# OpenPCR-combined-blockfront.net
KiCad netlist of a schematic drawn in EAGLE
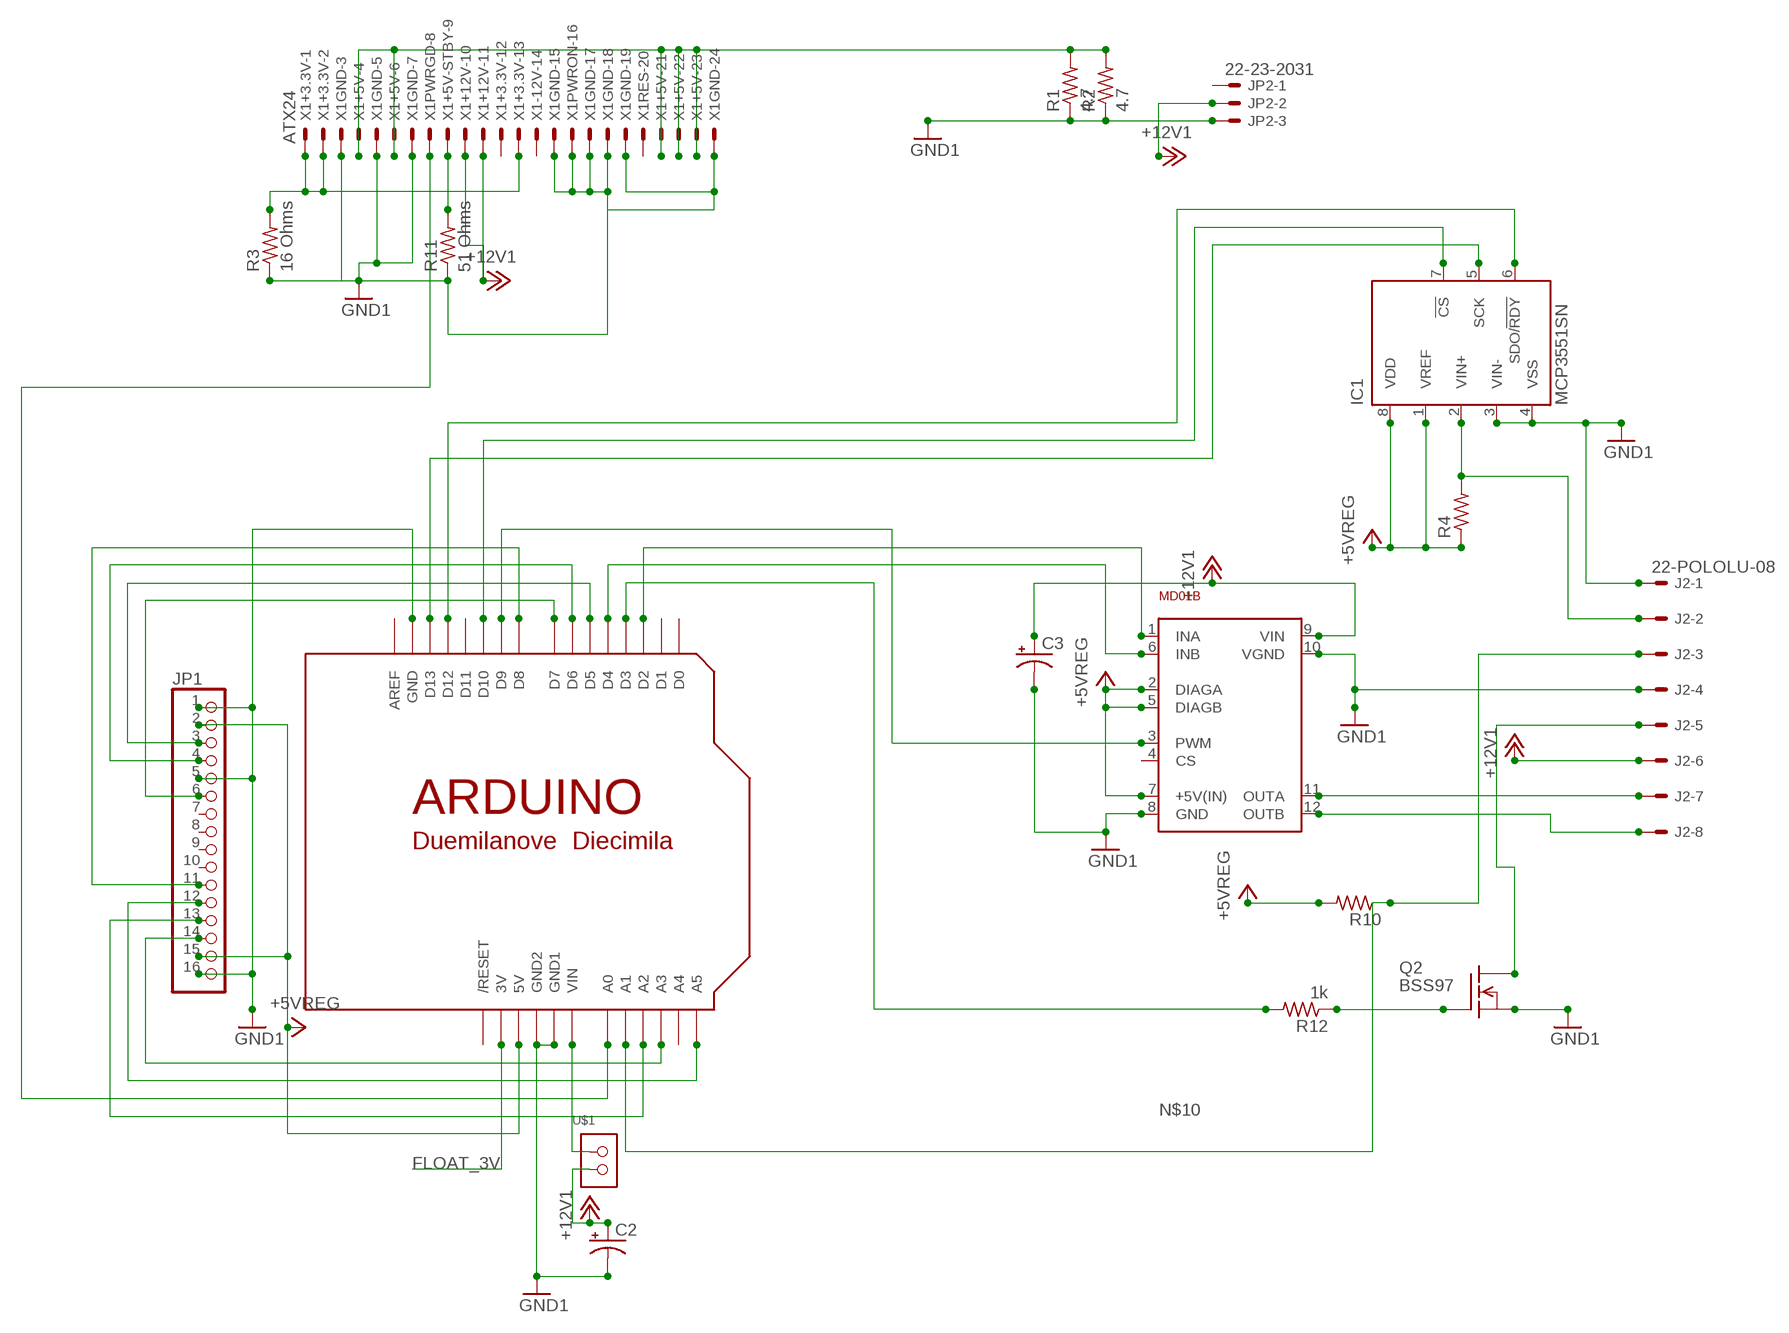
[diagram p0: schematic, sheet 1]

(export (version "E")
  (design (tool "Eeschema 10.0.6"))
  (components
    (comp (ref "C2")
      (value "CPOL-USE5-8.5")
      (footprint "eagle-import:E5-8,5")
      (libsource (lib "eagle-import") (part "CPOL-USE5-8.5"))
    )
    (comp (ref "C3")
      (value "CPOL-USE5-13")
      (footprint "eagle-import:E5-13")
      (libsource (lib "eagle-import") (part "CPOL-USE5-13"))
    )
    (comp (ref "IC1")
      (value "MCP3551SN")
      (footprint "eagle-import:SO-08")
      (fields (field (name "MPN") "MCP3551-E/SN"))
      (libsource (lib "eagle-import") (part "MCP355SN1"))
    )
    (comp (ref "J2")
      (value "22-POLOLU-08")
      (footprint "eagle-import:POLOLU-8")
      (libsource (lib "eagle-import") (part "22-?-08POLOLU"))
    )
    (comp (ref "JP1")
      (value "PINHD-1X16/90")
      (footprint "eagle-import:1X16_90")
      (libsource (lib "eagle-import") (part "PINHD-1X16/90"))
    )
    (comp (ref "JP2")
      (value "22-23-2031")
      (footprint "eagle-import:22-23-2031")
      (fields (field (name "MF") "MOLEX"))
      (libsource (lib "eagle-import") (part "22-23-2031"))
    )
    (comp (ref "MD01B")
      (value "VNH3SP30+4PIN")
      (footprint "eagle-import:VNH3SP30+4PIN")
      (libsource (lib "eagle-import") (part "VNH3SP30+4PIN"))
    )
    (comp (ref "Q2")
      (value "BSS97")
      (footprint "eagle-import:TO202")
      (libsource (lib "eagle-import") (part "BSS97"))
    )
    (comp (ref "R1")
      (value "4.7")
      (footprint "eagle-import:PR1")
      (libsource (lib "eagle-import") (part "PR1"))
    )
    (comp (ref "R2")
      (value "4.7")
      (footprint "eagle-import:PR1")
      (libsource (lib "eagle-import") (part "PR1"))
    )
    (comp (ref "R3")
      (value "16 Ohms")
      (footprint "eagle-import:0414_15")
      (libsource (lib "eagle-import") (part "resistor_R-US_0414/15"))
    )
    (comp (ref "R4")
      (value "R-US_0207/12")
      (footprint "eagle-import:0207_12")
      (libsource (lib "eagle-import") (part "resistor_R-US_0207/12"))
    )
    (comp (ref "R10")
      (value "R-US_0207/12")
      (footprint "eagle-import:0207_12")
      (libsource (lib "eagle-import") (part "resistor_R-US_0207/12"))
    )
    (comp (ref "R11")
      (value "51 Ohms")
      (footprint "eagle-import:0207_12")
      (libsource (lib "eagle-import") (part "R-US_0207/12"))
    )
    (comp (ref "R12")
      (value "1k")
      (footprint "eagle-import:0207_10")
      (libsource (lib "eagle-import") (part "resistor_R-US_0207/10"))
    )
    (comp (ref "U$1")
      (value "1X02")
      (footprint "eagle-import:1X02_1.1_UNSIGNED")
      (libsource (lib "eagle-import") (part "1X02"))
    )
    (comp (ref "U$3")
      (value "ARDUINODUEMILANOVE")
      (footprint "eagle-import:ARDUINO")
      (libsource (lib "eagle-import") (part "ARDUINODUEMILANOVE"))
    )
    (comp (ref "X1")
      (value "ATX24")
      (footprint "eagle-import:ATX24")
      (libsource (lib "eagle-import") (part "ATX24"))
    )
  )
  (nets
    (net (code "1") (name "+5VREG") (class "Default")
      (node (ref "IC1") (pin "1") (pinfunction "VREF_1") (pintype "input"))
      (node (ref "IC1") (pin "8") (pinfunction "VDD_8") (pintype "power_in"))
      (node (ref "JP1") (pin "15") (pinfunction "15_15") (pintype "passive"))
      (node (ref "JP1") (pin "2") (pinfunction "2_2") (pintype "passive"))
      (node (ref "MD01B") (pin "2") (pinfunction "DIAGA_2") (pintype "passive"))
      (node (ref "MD01B") (pin "5") (pinfunction "DIAGB_5") (pintype "passive"))
      (node (ref "MD01B") (pin "7") (pinfunction "+5V(IN)_7") (pintype "power_in"))
      (node (ref "R10") (pin "2") (pinfunction "2_2") (pintype "passive"))
      (node (ref "R4") (pin "1") (pinfunction "1_1") (pintype "passive"))
      (node (ref "U$3") (pin "5V") (pinfunction "5V_5V") (pintype "power_in"))
    )
    (net (code "2") (name "+12V1") (class "Default")
      (node (ref "C2") (pin "+") (pinfunction "+_+") (pintype "passive"))
      (node (ref "C3") (pin "+") (pinfunction "+_+") (pintype "passive"))
      (node (ref "J2") (pin "6") (pinfunction "S_6") (pintype "passive"))
      (node (ref "JP2") (pin "2") (pinfunction "S_2") (pintype "passive"))
      (node (ref "MD01B") (pin "9") (pinfunction "VIN_9") (pintype "power_in"))
      (node (ref "U$1") (pin "2") (pinfunction "2_2") (pintype "passive"))
      (node (ref "X1") (pin "10") (pinfunction "S_10") (pintype "passive"))
      (node (ref "X1") (pin "11") (pinfunction "S_11") (pintype "passive"))
    )
    (net (code "3") (name "/FLOAT_3V") (class "Default")
      (node (ref "U$3") (pin "3V") (pinfunction "3V_3V") (pintype "power_in"))
    )
    (net (code "4") (name "/N$10") (class "Default")
      (node (ref "JP1") (pin "13") (pinfunction "13_13") (pintype "passive"))
      (node (ref "U$3") (pin "A2") (pinfunction "A2_A2") (pintype "bidirectional"))
    )
    (net (code "5") (name "GND1") (class "Default")
      (node (ref "C2") (pin "-") (pinfunction "-_-") (pintype "passive"))
      (node (ref "C3") (pin "-") (pinfunction "-_-") (pintype "passive"))
      (node (ref "IC1") (pin "3") (pinfunction "VIN-_3") (pintype "input"))
      (node (ref "IC1") (pin "4") (pinfunction "VSS_4") (pintype "power_in"))
      (node (ref "J2") (pin "1") (pinfunction "S_1") (pintype "passive"))
      (node (ref "J2") (pin "4") (pinfunction "S_4") (pintype "passive"))
      (node (ref "JP1") (pin "1") (pinfunction "1_1") (pintype "passive"))
      (node (ref "JP1") (pin "16") (pinfunction "16_16") (pintype "passive"))
      (node (ref "JP1") (pin "5") (pinfunction "5_5") (pintype "passive"))
      (node (ref "JP2") (pin "3") (pinfunction "S_3") (pintype "passive"))
      (node (ref "MD01B") (pin "10") (pinfunction "VGND_10") (pintype "power_in"))
      (node (ref "MD01B") (pin "8") (pinfunction "GND_8") (pintype "power_in"))
      (node (ref "Q2") (pin "1") (pinfunction "S_1") (pintype "passive"))
      (node (ref "R1") (pin "1") (pinfunction "1_1") (pintype "passive"))
      (node (ref "R11") (pin "1") (pinfunction "1_1") (pintype "passive"))
      (node (ref "R2") (pin "1") (pinfunction "1_1") (pintype "passive"))
      (node (ref "R3") (pin "1") (pinfunction "1_1") (pintype "passive"))
      (node (ref "U$3") (pin "GND") (pinfunction "GND_GND") (pintype "power_in"))
      (node (ref "U$3") (pin "GND1") (pinfunction "GND1_GND1") (pintype "power_in"))
      (node (ref "U$3") (pin "GND2") (pinfunction "GND2_GND2") (pintype "power_in"))
      (node (ref "X1") (pin "15") (pinfunction "S_15") (pintype "passive"))
      (node (ref "X1") (pin "16") (pinfunction "S_16") (pintype "passive"))
      (node (ref "X1") (pin "17") (pinfunction "S_17") (pintype "passive"))
      (node (ref "X1") (pin "18") (pinfunction "S_18") (pintype "passive"))
      (node (ref "X1") (pin "19") (pinfunction "S_19") (pintype "passive"))
      (node (ref "X1") (pin "24") (pinfunction "S_24") (pintype "passive"))
      (node (ref "X1") (pin "3") (pinfunction "S_3") (pintype "passive"))
      (node (ref "X1") (pin "5") (pinfunction "S_5") (pintype "passive"))
      (node (ref "X1") (pin "7") (pinfunction "S_7") (pintype "passive"))
    )
    (net (code "6") (name "Net-(IC1-SCK)") (class "Default")
      (node (ref "IC1") (pin "5") (pinfunction "SCK_5") (pintype "input"))
      (node (ref "U$3") (pin "D13") (pinfunction "D13_D13") (pintype "bidirectional"))
    )
    (net (code "7") (name "Net-(IC1-SDO{slash}~{RDY})") (class "Default")
      (node (ref "IC1") (pin "6") (pinfunction "SDO/~{RDY}_6") (pintype "output"))
      (node (ref "U$3") (pin "D12") (pinfunction "D12_D12") (pintype "bidirectional"))
    )
    (net (code "8") (name "Net-(IC1-VIN+)") (class "Default")
      (node (ref "IC1") (pin "2") (pinfunction "VIN+_2") (pintype "input"))
      (node (ref "J2") (pin "2") (pinfunction "S_2") (pintype "passive"))
      (node (ref "R4") (pin "2") (pinfunction "2_2") (pintype "passive"))
    )
    (net (code "9") (name "Net-(IC1-~{CS})") (class "Default")
      (node (ref "IC1") (pin "7") (pinfunction "~{CS}_7") (pintype "input"))
      (node (ref "U$3") (pin "D10") (pinfunction "D10_D10") (pintype "bidirectional"))
    )
    (net (code "10") (name "Net-(J2C-S)") (class "Default")
      (node (ref "J2") (pin "3") (pinfunction "S_3") (pintype "passive"))
      (node (ref "R10") (pin "1") (pinfunction "1_1") (pintype "passive"))
      (node (ref "U$3") (pin "A1") (pinfunction "A1_A1") (pintype "bidirectional"))
    )
    (net (code "11") (name "Net-(J2E-S)") (class "Default")
      (node (ref "J2") (pin "5") (pinfunction "S_5") (pintype "passive"))
      (node (ref "Q2") (pin "2") (pinfunction "D_2") (pintype "passive"))
    )
    (net (code "12") (name "Net-(J2G-S)") (class "Default")
      (node (ref "J2") (pin "7") (pinfunction "S_7") (pintype "passive"))
      (node (ref "MD01B") (pin "11") (pinfunction "OUTA_11") (pintype "passive"))
    )
    (net (code "13") (name "Net-(J2H-S)") (class "Default")
      (node (ref "J2") (pin "8") (pinfunction "S_8") (pintype "passive"))
      (node (ref "MD01B") (pin "12") (pinfunction "OUTB_12") (pintype "passive"))
    )
    (net (code "14") (name "Net-(JP1-Pad3)") (class "Default")
      (node (ref "JP1") (pin "3") (pinfunction "3_3") (pintype "passive"))
      (node (ref "U$3") (pin "D5") (pinfunction "D5_D5") (pintype "bidirectional"))
    )
    (net (code "15") (name "Net-(JP1-Pad4)") (class "Default")
      (node (ref "JP1") (pin "4") (pinfunction "4_4") (pintype "passive"))
      (node (ref "U$3") (pin "D6") (pinfunction "D6_D6") (pintype "bidirectional"))
    )
    (net (code "16") (name "Net-(JP1-Pad6)") (class "Default")
      (node (ref "JP1") (pin "6") (pinfunction "6_6") (pintype "passive"))
      (node (ref "U$3") (pin "D7") (pinfunction "D7_D7") (pintype "bidirectional"))
    )
    (net (code "17") (name "Net-(JP1-Pad11)") (class "Default")
      (node (ref "JP1") (pin "11") (pinfunction "11_11") (pintype "passive"))
      (node (ref "U$3") (pin "D8") (pinfunction "D8_D8") (pintype "bidirectional"))
    )
    (net (code "18") (name "Net-(JP1-Pad12)") (class "Default")
      (node (ref "JP1") (pin "12") (pinfunction "12_12") (pintype "passive"))
      (node (ref "U$3") (pin "A5") (pinfunction "A5_A5") (pintype "bidirectional"))
    )
    (net (code "19") (name "Net-(JP1-Pad14)") (class "Default")
      (node (ref "JP1") (pin "14") (pinfunction "14_14") (pintype "passive"))
      (node (ref "U$3") (pin "A3") (pinfunction "A3_A3") (pintype "bidirectional"))
    )
    (net (code "20") (name "Net-(MD01B-INA)") (class "Default")
      (node (ref "MD01B") (pin "1") (pinfunction "INA_1") (pintype "passive"))
      (node (ref "U$3") (pin "D2") (pinfunction "D2_D2") (pintype "bidirectional"))
    )
    (net (code "21") (name "Net-(MD01B-INB)") (class "Default")
      (node (ref "MD01B") (pin "6") (pinfunction "INB_6") (pintype "passive"))
      (node (ref "U$3") (pin "D4") (pinfunction "D4_D4") (pintype "bidirectional"))
    )
    (net (code "22") (name "Net-(MD01B-PWM)") (class "Default")
      (node (ref "MD01B") (pin "3") (pinfunction "PWM_3") (pintype "passive"))
      (node (ref "U$3") (pin "D9") (pinfunction "D9_D9") (pintype "bidirectional"))
    )
    (net (code "23") (name "Net-(Q2-G)") (class "Default")
      (node (ref "Q2") (pin "3") (pinfunction "G_3") (pintype "passive"))
      (node (ref "R12") (pin "1") (pinfunction "1_1") (pintype "passive"))
    )
    (net (code "24") (name "Net-(R12-Pad2)") (class "Default")
      (node (ref "R12") (pin "2") (pinfunction "2_2") (pintype "passive"))
      (node (ref "U$3") (pin "D3") (pinfunction "D3_D3") (pintype "bidirectional"))
    )
    (net (code "25") (name "Net-(U$1-Pad1)") (class "Default")
      (node (ref "U$1") (pin "1") (pinfunction "1_1") (pintype "passive"))
      (node (ref "U$3") (pin "VIN") (pinfunction "VIN_VIN") (pintype "power_in"))
    )
    (net (code "26") (name "Net-(X1C-S)") (class "Default")
      (node (ref "R3") (pin "2") (pinfunction "2_2") (pintype "passive"))
      (node (ref "X1") (pin "1") (pinfunction "S_1") (pintype "passive"))
      (node (ref "X1") (pin "13") (pinfunction "S_13") (pintype "passive"))
      (node (ref "X1") (pin "2") (pinfunction "S_2") (pintype "passive"))
    )
    (net (code "27") (name "Net-(X1G-S)") (class "Default")
      (node (ref "R1") (pin "2") (pinfunction "2_2") (pintype "passive"))
      (node (ref "R2") (pin "2") (pinfunction "2_2") (pintype "passive"))
      (node (ref "X1") (pin "21") (pinfunction "S_21") (pintype "passive"))
      (node (ref "X1") (pin "22") (pinfunction "S_22") (pintype "passive"))
      (node (ref "X1") (pin "23") (pinfunction "S_23") (pintype "passive"))
      (node (ref "X1") (pin "4") (pinfunction "S_4") (pintype "passive"))
      (node (ref "X1") (pin "6") (pinfunction "S_6") (pintype "passive"))
    )
    (net (code "28") (name "Net-(X1L-S)") (class "Default")
      (node (ref "R11") (pin "2") (pinfunction "2_2") (pintype "passive"))
      (node (ref "X1") (pin "9") (pinfunction "S_9") (pintype "passive"))
    )
    (net (code "29") (name "Net-(X1V-S)") (class "Default")
      (node (ref "U$3") (pin "A0") (pinfunction "A0_A0") (pintype "bidirectional"))
      (node (ref "X1") (pin "8") (pinfunction "S_8") (pintype "passive"))
    )
    (net (code "30") (name "unconnected-(JP1-Pad7)") (class "Default")
      (node (ref "JP1") (pin "7") (pinfunction "7_7") (pintype "passive"))
    )
    (net (code "31") (name "unconnected-(JP1-Pad8)") (class "Default")
      (node (ref "JP1") (pin "8") (pinfunction "8_8") (pintype "passive"))
    )
    (net (code "32") (name "unconnected-(JP1-Pad9)") (class "Default")
      (node (ref "JP1") (pin "9") (pinfunction "9_9") (pintype "passive"))
    )
    (net (code "33") (name "unconnected-(JP1-Pad10)") (class "Default")
      (node (ref "JP1") (pin "10") (pinfunction "10_10") (pintype "passive"))
    )
    (net (code "34") (name "unconnected-(JP2A-S-Pad1)") (class "Default")
      (node (ref "JP2") (pin "1") (pinfunction "S_1") (pintype "passive"))
    )
    (net (code "35") (name "unconnected-(MD01B-CS-Pad4)") (class "Default")
      (node (ref "MD01B") (pin "4") (pinfunction "CS_4") (pintype "passive"))
    )
    (net (code "36") (name "unconnected-(U$3-PadA4)") (class "Default")
      (node (ref "U$3") (pin "A4") (pinfunction "A4_A4") (pintype "bidirectional"))
    )
    (net (code "37") (name "unconnected-(U$3-PadAREF)") (class "Default")
      (node (ref "U$3") (pin "AREF") (pinfunction "AREF_AREF") (pintype "bidirectional"))
    )
    (net (code "38") (name "unconnected-(U$3-PadD0)") (class "Default")
      (node (ref "U$3") (pin "D0") (pinfunction "D0_D0") (pintype "bidirectional"))
    )
    (net (code "39") (name "unconnected-(U$3-PadD1)") (class "Default")
      (node (ref "U$3") (pin "D1") (pinfunction "D1_D1") (pintype "bidirectional"))
    )
    (net (code "40") (name "unconnected-(U$3-PadD11)") (class "Default")
      (node (ref "U$3") (pin "D11") (pinfunction "D11_D11") (pintype "bidirectional"))
    )
    (net (code "41") (name "unconnected-(U$3-{slash}RESET-PadRESET)") (class "Default")
      (node (ref "U$3") (pin "RESET") (pinfunction "/RESET_RESET") (pintype "bidirectional"))
    )
    (net (code "42") (name "unconnected-(X1D-S-Pad12)") (class "Default")
      (node (ref "X1") (pin "12") (pinfunction "S_12") (pintype "passive"))
    )
    (net (code "43") (name "unconnected-(X1M-S-Pad14)") (class "Default")
      (node (ref "X1") (pin "14") (pinfunction "S_14") (pintype "passive"))
    )
    (net (code "44") (name "unconnected-(X1X-S-Pad20)") (class "Default")
      (node (ref "X1") (pin "20") (pinfunction "S_20") (pintype "passive"))
    )
  )
)
